# shaker.net
KiCad netlist of a schematic drawn in EAGLE
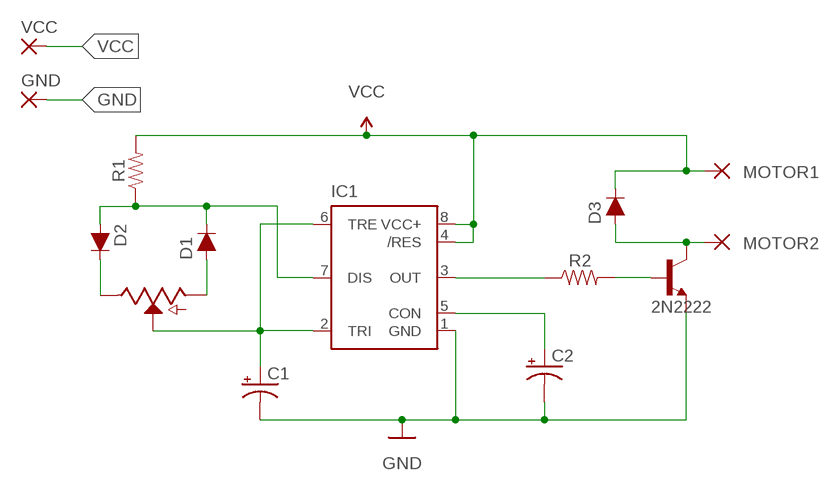
[diagram p0: schematic, sheet 1]

(export (version "E")
  (design (tool "Eeschema 10.0.6"))
  (components
    (comp (ref "2N2222")
      (value "200mA/40V")
      (footprint "eagle-import:TO-92")
      (libsource (lib "eagle-import") (part "TRANS_NPN2N2222"))
    )
    (comp (ref "C1")
      (value "CAPACITOR_5MM")
      (footprint "eagle-import:CAPPRD508W65D500H1100B")
      (libsource (lib "eagle-import") (part "CAPACITOR_5MM"))
    )
    (comp (ref "C2")
      (value "100nF")
      (footprint "eagle-import:CAPPRD508W65D500H1100B")
      (libsource (lib "eagle-import") (part "CAPACITOR_5MM"))
    )
    (comp (ref "D1")
      (value "DIODEDEFAULT")
      (footprint "eagle-import:DIODE")
      (libsource (lib "eagle-import") (part "DIODEDEFAULT"))
    )
    (comp (ref "D2")
      (value "DIODEDEFAULT")
      (footprint "eagle-import:DIODE")
      (libsource (lib "eagle-import") (part "DIODEDEFAULT"))
    )
    (comp (ref "D3")
      (value "DIODEDEFAULT")
      (footprint "eagle-import:DIODE")
      (libsource (lib "eagle-import") (part "DIODEDEFAULT"))
    )
    (comp (ref "GND")
      (value "3,81/1,4")
      (footprint "eagle-import:3,81_1,4")
      (libsource (lib "eagle-import") (part "3,81/1,4"))
    )
    (comp (ref "IC1")
      (value "555")
      (footprint "eagle-import:DIP8")
      (libsource (lib "eagle-import") (part "555TEXAS_INSTRUMENTS"))
    )
    (comp (ref "MOTOR1")
      (value "3,81/1,4")
      (footprint "eagle-import:3,81_1,4")
      (libsource (lib "eagle-import") (part "3,81/1,4"))
    )
    (comp (ref "MOTOR2")
      (value "3,81/1,4")
      (footprint "eagle-import:3,81_1,4")
      (libsource (lib "eagle-import") (part "3,81/1,4"))
    )
    (comp (ref "R1")
      (value "RESISTORDEFAULT")
      (footprint "eagle-import:RESISTOR")
      (libsource (lib "eagle-import") (part "RESISTORDEFAULT"))
    )
    (comp (ref "R2")
      (value "1k")
      (footprint "eagle-import:RESISTOR")
      (libsource (lib "eagle-import") (part "RESISTORDEFAULT"))
    )
    (comp (ref "VCC")
      (value "3,81/1,4")
      (footprint "eagle-import:3,81_1,4")
      (libsource (lib "eagle-import") (part "3,81/1,4"))
    )
    (comp (ref "VR1")
      (value "10k")
      (footprint "eagle-import:POTENTIOMETER")
      (libsource (lib "eagle-import") (part "POTENTIOMETERDEFAULT"))
    )
  )
  (nets
    (net (code "1") (name "GND") (class "Default")
      (node (ref "2N2222") (pin "1") (pinfunction "E_1") (pintype "passive"))
      (node (ref "C1") (pin "2") (pinfunction "-_2") (pintype "passive"))
      (node (ref "C2") (pin "2") (pinfunction "-_2") (pintype "passive"))
      (node (ref "GND") (pin "1") (pinfunction "P_1") (pintype "passive"))
      (node (ref "IC1") (pin "1") (pinfunction "GND_1") (pintype "power_in"))
    )
    (net (code "2") (name "Net-(2N2222-B)") (class "Default")
      (node (ref "2N2222") (pin "2") (pinfunction "B_2") (pintype "passive"))
      (node (ref "R2") (pin "2") (pinfunction "2_2") (pintype "passive"))
    )
    (net (code "3") (name "Net-(2N2222-C)") (class "Default")
      (node (ref "2N2222") (pin "3") (pinfunction "C_3") (pintype "passive"))
      (node (ref "D3") (pin "ANODE") (pinfunction "A_ANODE") (pintype "passive"))
      (node (ref "MOTOR2") (pin "1") (pinfunction "P_1") (pintype "passive"))
    )
    (net (code "4") (name "Net-(C1-+)") (class "Default")
      (node (ref "C1") (pin "1") (pinfunction "+_1") (pintype "passive"))
      (node (ref "IC1") (pin "2") (pinfunction "TRI_2") (pintype "input"))
      (node (ref "IC1") (pin "6") (pinfunction "TRE_6") (pintype "input"))
      (node (ref "VR1") (pin "C") (pinfunction "CENTER_C") (pintype "passive"))
    )
    (net (code "5") (name "Net-(C2-+)") (class "Default")
      (node (ref "C2") (pin "1") (pinfunction "+_1") (pintype "passive"))
      (node (ref "IC1") (pin "5") (pinfunction "CON_5") (pintype "input"))
    )
    (net (code "6") (name "Net-(D1-A)") (class "Default")
      (node (ref "D1") (pin "ANODE") (pinfunction "A_ANODE") (pintype "passive"))
      (node (ref "VR1") (pin "A") (pinfunction "A_A") (pintype "passive"))
    )
    (net (code "7") (name "Net-(D1-C)") (class "Default")
      (node (ref "D1") (pin "CATHODE") (pinfunction "C_CATHODE") (pintype "passive"))
      (node (ref "D2") (pin "ANODE") (pinfunction "A_ANODE") (pintype "passive"))
      (node (ref "IC1") (pin "7") (pinfunction "DIS_7") (pintype "input"))
      (node (ref "R1") (pin "1") (pinfunction "1_1") (pintype "passive"))
    )
    (net (code "8") (name "Net-(D2-C)") (class "Default")
      (node (ref "D2") (pin "CATHODE") (pinfunction "C_CATHODE") (pintype "passive"))
      (node (ref "VR1") (pin "B") (pinfunction "E_B") (pintype "passive"))
    )
    (net (code "9") (name "Net-(IC1-OUT)") (class "Default")
      (node (ref "IC1") (pin "3") (pinfunction "OUT_3") (pintype "output"))
      (node (ref "R2") (pin "1") (pinfunction "1_1") (pintype "passive"))
    )
    (net (code "10") (name "VCC") (class "Default")
      (node (ref "D3") (pin "CATHODE") (pinfunction "C_CATHODE") (pintype "passive"))
      (node (ref "IC1") (pin "4") (pinfunction "/RES_4") (pintype "input"))
      (node (ref "IC1") (pin "8") (pinfunction "VCC+_8") (pintype "power_in"))
      (node (ref "MOTOR1") (pin "1") (pinfunction "P_1") (pintype "passive"))
      (node (ref "R1") (pin "2") (pinfunction "2_2") (pintype "passive"))
      (node (ref "VCC") (pin "1") (pinfunction "P_1") (pintype "passive"))
    )
  )
)
